# control-opto.net
KiCad netlist of a schematic drawn in EAGLE
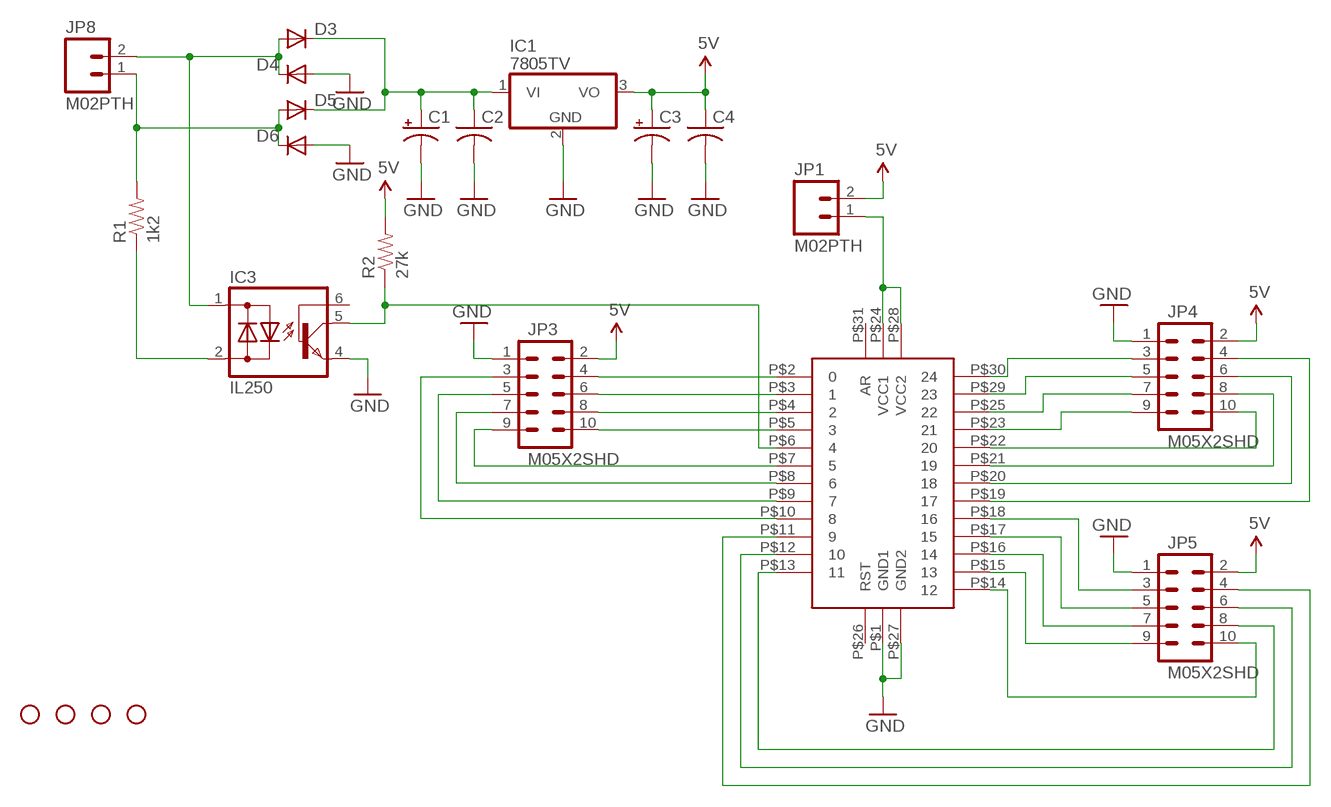
[diagram p0: schematic, sheet 1]

(export (version "E")
  (design (tool "Eeschema 10.0.6"))
  (components
    (comp (ref "C1")
      (value "CPOL-USE3.5-10")
      (footprint "eagle-import:E3,5-10")
      (libsource (lib "eagle-import") (part "CPOL-USE3.5-10"))
    )
    (comp (ref "C2")
      (value "C-US025-030X050")
      (footprint "eagle-import:C025-030X050")
      (libsource (lib "eagle-import") (part "C-US025-030X050"))
    )
    (comp (ref "C3")
      (value "CPOL-USE3.5-10")
      (footprint "eagle-import:E3,5-10")
      (libsource (lib "eagle-import") (part "CPOL-USE3.5-10"))
    )
    (comp (ref "C4")
      (value "C-US025-030X050")
      (footprint "eagle-import:C025-030X050")
      (libsource (lib "eagle-import") (part "C-US025-030X050"))
    )
    (comp (ref "D3")
      (value "DIODEPTH")
      (footprint "eagle-import:DIODE-1N4001")
      (libsource (lib "eagle-import") (part "DIODEPTH"))
    )
    (comp (ref "D4")
      (value "DIODEPTH")
      (footprint "eagle-import:DIODE-1N4001")
      (libsource (lib "eagle-import") (part "DIODEPTH"))
    )
    (comp (ref "D5")
      (value "DIODEPTH")
      (footprint "eagle-import:DIODE-1N4001")
      (libsource (lib "eagle-import") (part "DIODEPTH"))
    )
    (comp (ref "D6")
      (value "DIODEPTH")
      (footprint "eagle-import:DIODE-1N4001")
      (libsource (lib "eagle-import") (part "DIODEPTH"))
    )
    (comp (ref "IC1")
      (value "7805TV")
      (footprint "eagle-import:TO220V")
      (libsource (lib "eagle-import") (part "78TV05"))
    )
    (comp (ref "IC2")
      (value "TEENSY2")
      (footprint "eagle-import:TEENSY2")
      (libsource (lib "eagle-import") (part "TEENSY2"))
    )
    (comp (ref "IC3")
      (value "IL250")
      (footprint "eagle-import:DIL06")
      (fields (field (name "MF") "VISHAY/TELEFUNKEN"))
      (libsource (lib "eagle-import") (part "IL250"))
    )
    (comp (ref "JP1")
      (value "M02PTH")
      (footprint "eagle-import:1X02")
      (libsource (lib "eagle-import") (part "M02PTH"))
    )
    (comp (ref "JP3")
      (value "M05X2SHD")
      (footprint "eagle-import:2X5-SHROUDED")
      (libsource (lib "eagle-import") (part "M05X2SHD"))
    )
    (comp (ref "JP4")
      (value "M05X2SHD")
      (footprint "eagle-import:2X5-SHROUDED")
      (libsource (lib "eagle-import") (part "M05X2SHD"))
    )
    (comp (ref "JP5")
      (value "M05X2SHD")
      (footprint "eagle-import:2X5-SHROUDED")
      (libsource (lib "eagle-import") (part "M05X2SHD"))
    )
    (comp (ref "JP8")
      (value "M02PTH")
      (footprint "eagle-import:1X02")
      (libsource (lib "eagle-import") (part "M02PTH"))
    )
    (comp (ref "R1")
      (value "1k2")
      (footprint "eagle-import:AXIAL-0.4")
      (libsource (lib "eagle-import") (part "RESISTORPTH-1/4W"))
    )
    (comp (ref "R2")
      (value "27k")
      (footprint "eagle-import:AXIAL-0.4")
      (libsource (lib "eagle-import") (part "RESISTORPTH-1/4W"))
    )
    (comp (ref "STANDOFF1")
      (value "STAND-OFF")
      (footprint "eagle-import:STAND-OFF")
      (libsource (lib "eagle-import") (part "STAND-OFF"))
    )
    (comp (ref "STANDOFF2")
      (value "STAND-OFF")
      (footprint "eagle-import:STAND-OFF")
      (libsource (lib "eagle-import") (part "STAND-OFF"))
    )
    (comp (ref "STANDOFF3")
      (value "STAND-OFF")
      (footprint "eagle-import:STAND-OFF")
      (libsource (lib "eagle-import") (part "STAND-OFF"))
    )
    (comp (ref "STANDOFF4")
      (value "STAND-OFF")
      (footprint "eagle-import:STAND-OFF")
      (libsource (lib "eagle-import") (part "STAND-OFF"))
    )
  )
  (nets
    (net (code "1") (name "5V") (class "Default")
      (node (ref "C3") (pin "+") (pinfunction "+_+") (pintype "passive"))
      (node (ref "C4") (pin "1") (pinfunction "1_1") (pintype "passive"))
      (node (ref "IC1") (pin "3") (pinfunction "VO_3") (pintype "passive"))
      (node (ref "JP1") (pin "2") (pinfunction "2_2") (pintype "passive"))
      (node (ref "JP3") (pin "2") (pinfunction "2_2") (pintype "passive"))
      (node (ref "JP4") (pin "2") (pinfunction "2_2") (pintype "passive"))
      (node (ref "JP5") (pin "2") (pinfunction "2_2") (pintype "passive"))
      (node (ref "R2") (pin "P$2") (pinfunction "2_P$2") (pintype "passive"))
    )
    (net (code "2") (name "GND") (class "Default")
      (node (ref "C1") (pin "-") (pinfunction "-_-") (pintype "passive"))
      (node (ref "C2") (pin "2") (pinfunction "2_2") (pintype "passive"))
      (node (ref "C3") (pin "-") (pinfunction "-_-") (pintype "passive"))
      (node (ref "C4") (pin "2") (pinfunction "2_2") (pintype "passive"))
      (node (ref "D4") (pin "A") (pinfunction "A_A") (pintype "passive"))
      (node (ref "D6") (pin "A") (pinfunction "A_A") (pintype "passive"))
      (node (ref "IC1") (pin "2") (pinfunction "GND_2") (pintype "passive"))
      (node (ref "IC2") (pin "P$1") (pinfunction "GND1_P$1") (pintype "bidirectional"))
      (node (ref "IC2") (pin "P$27") (pinfunction "GND2_P$27") (pintype "bidirectional"))
      (node (ref "IC3") (pin "4") (pinfunction "E_4") (pintype "passive"))
      (node (ref "JP3") (pin "1") (pinfunction "1_1") (pintype "passive"))
      (node (ref "JP4") (pin "1") (pinfunction "1_1") (pintype "passive"))
      (node (ref "JP5") (pin "1") (pinfunction "1_1") (pintype "passive"))
    )
    (net (code "3") (name "Net-(IC1-VI)") (class "Default")
      (node (ref "C1") (pin "+") (pinfunction "+_+") (pintype "passive"))
      (node (ref "C2") (pin "1") (pinfunction "1_1") (pintype "passive"))
      (node (ref "D3") (pin "C") (pinfunction "C_C") (pintype "passive"))
      (node (ref "D5") (pin "C") (pinfunction "C_C") (pintype "passive"))
      (node (ref "IC1") (pin "1") (pinfunction "VI_1") (pintype "input"))
    )
    (net (code "4") (name "Net-(IC2-0)") (class "Default")
      (node (ref "IC2") (pin "P$2") (pinfunction "0_P$2") (pintype "bidirectional"))
      (node (ref "JP3") (pin "4") (pinfunction "4_4") (pintype "passive"))
    )
    (net (code "5") (name "Net-(IC2-1)") (class "Default")
      (node (ref "IC2") (pin "P$3") (pinfunction "1_P$3") (pintype "bidirectional"))
      (node (ref "JP3") (pin "6") (pinfunction "6_6") (pintype "passive"))
    )
    (net (code "6") (name "Net-(IC2-2)") (class "Default")
      (node (ref "IC2") (pin "P$4") (pinfunction "2_P$4") (pintype "bidirectional"))
      (node (ref "JP3") (pin "8") (pinfunction "8_8") (pintype "passive"))
    )
    (net (code "7") (name "Net-(IC2-3)") (class "Default")
      (node (ref "IC2") (pin "P$5") (pinfunction "3_P$5") (pintype "bidirectional"))
      (node (ref "JP3") (pin "10") (pinfunction "10_10") (pintype "passive"))
    )
    (net (code "8") (name "Net-(IC2-4)") (class "Default")
      (node (ref "IC2") (pin "P$6") (pinfunction "4_P$6") (pintype "bidirectional"))
      (node (ref "IC3") (pin "5") (pinfunction "C_5") (pintype "passive"))
      (node (ref "R2") (pin "P$1") (pinfunction "1_P$1") (pintype "passive"))
    )
    (net (code "9") (name "Net-(IC2-5)") (class "Default")
      (node (ref "IC2") (pin "P$7") (pinfunction "5_P$7") (pintype "bidirectional"))
      (node (ref "JP3") (pin "9") (pinfunction "9_9") (pintype "passive"))
    )
    (net (code "10") (name "Net-(IC2-6)") (class "Default")
      (node (ref "IC2") (pin "P$8") (pinfunction "6_P$8") (pintype "bidirectional"))
      (node (ref "JP3") (pin "7") (pinfunction "7_7") (pintype "passive"))
    )
    (net (code "11") (name "Net-(IC2-7)") (class "Default")
      (node (ref "IC2") (pin "P$9") (pinfunction "7_P$9") (pintype "bidirectional"))
      (node (ref "JP3") (pin "5") (pinfunction "5_5") (pintype "passive"))
    )
    (net (code "12") (name "Net-(IC2-8)") (class "Default")
      (node (ref "IC2") (pin "P$10") (pinfunction "8_P$10") (pintype "bidirectional"))
      (node (ref "JP3") (pin "3") (pinfunction "3_3") (pintype "passive"))
    )
    (net (code "13") (name "Net-(IC2-9)") (class "Default")
      (node (ref "IC2") (pin "P$11") (pinfunction "9_P$11") (pintype "bidirectional"))
      (node (ref "JP5") (pin "4") (pinfunction "4_4") (pintype "passive"))
    )
    (net (code "14") (name "Net-(IC2-10)") (class "Default")
      (node (ref "IC2") (pin "P$12") (pinfunction "10_P$12") (pintype "bidirectional"))
      (node (ref "JP5") (pin "6") (pinfunction "6_6") (pintype "passive"))
    )
    (net (code "15") (name "Net-(IC2-11)") (class "Default")
      (node (ref "IC2") (pin "P$13") (pinfunction "11_P$13") (pintype "bidirectional"))
      (node (ref "JP5") (pin "8") (pinfunction "8_8") (pintype "passive"))
    )
    (net (code "16") (name "Net-(IC2-12)") (class "Default")
      (node (ref "IC2") (pin "P$14") (pinfunction "12_P$14") (pintype "bidirectional"))
      (node (ref "JP5") (pin "10") (pinfunction "10_10") (pintype "passive"))
    )
    (net (code "17") (name "Net-(IC2-13)") (class "Default")
      (node (ref "IC2") (pin "P$15") (pinfunction "13_P$15") (pintype "bidirectional"))
      (node (ref "JP5") (pin "9") (pinfunction "9_9") (pintype "passive"))
    )
    (net (code "18") (name "Net-(IC2-14)") (class "Default")
      (node (ref "IC2") (pin "P$16") (pinfunction "14_P$16") (pintype "bidirectional"))
      (node (ref "JP5") (pin "7") (pinfunction "7_7") (pintype "passive"))
    )
    (net (code "19") (name "Net-(IC2-15)") (class "Default")
      (node (ref "IC2") (pin "P$17") (pinfunction "15_P$17") (pintype "bidirectional"))
      (node (ref "JP5") (pin "5") (pinfunction "5_5") (pintype "passive"))
    )
    (net (code "20") (name "Net-(IC2-16)") (class "Default")
      (node (ref "IC2") (pin "P$18") (pinfunction "16_P$18") (pintype "bidirectional"))
      (node (ref "JP5") (pin "3") (pinfunction "3_3") (pintype "passive"))
    )
    (net (code "21") (name "Net-(IC2-17)") (class "Default")
      (node (ref "IC2") (pin "P$19") (pinfunction "17_P$19") (pintype "bidirectional"))
      (node (ref "JP4") (pin "4") (pinfunction "4_4") (pintype "passive"))
    )
    (net (code "22") (name "Net-(IC2-18)") (class "Default")
      (node (ref "IC2") (pin "P$20") (pinfunction "18_P$20") (pintype "bidirectional"))
      (node (ref "JP4") (pin "6") (pinfunction "6_6") (pintype "passive"))
    )
    (net (code "23") (name "Net-(IC2-19)") (class "Default")
      (node (ref "IC2") (pin "P$21") (pinfunction "19_P$21") (pintype "bidirectional"))
      (node (ref "JP4") (pin "8") (pinfunction "8_8") (pintype "passive"))
    )
    (net (code "24") (name "Net-(IC2-20)") (class "Default")
      (node (ref "IC2") (pin "P$22") (pinfunction "20_P$22") (pintype "bidirectional"))
      (node (ref "JP4") (pin "10") (pinfunction "10_10") (pintype "passive"))
    )
    (net (code "25") (name "Net-(IC2-21)") (class "Default")
      (node (ref "IC2") (pin "P$23") (pinfunction "21_P$23") (pintype "bidirectional"))
      (node (ref "JP4") (pin "9") (pinfunction "9_9") (pintype "passive"))
    )
    (net (code "26") (name "Net-(IC2-22)") (class "Default")
      (node (ref "IC2") (pin "P$25") (pinfunction "22_P$25") (pintype "bidirectional"))
      (node (ref "JP4") (pin "7") (pinfunction "7_7") (pintype "passive"))
    )
    (net (code "27") (name "Net-(IC2-23)") (class "Default")
      (node (ref "IC2") (pin "P$29") (pinfunction "23_P$29") (pintype "bidirectional"))
      (node (ref "JP4") (pin "5") (pinfunction "5_5") (pintype "passive"))
    )
    (net (code "28") (name "Net-(IC2-24)") (class "Default")
      (node (ref "IC2") (pin "P$30") (pinfunction "24_P$30") (pintype "bidirectional"))
      (node (ref "JP4") (pin "3") (pinfunction "3_3") (pintype "passive"))
    )
    (net (code "29") (name "Net-(IC2-VCC1)") (class "Default")
      (node (ref "IC2") (pin "P$24") (pinfunction "VCC1_P$24") (pintype "bidirectional"))
      (node (ref "IC2") (pin "P$28") (pinfunction "VCC2_P$28") (pintype "bidirectional"))
      (node (ref "JP1") (pin "1") (pinfunction "1_1") (pintype "passive"))
    )
    (net (code "30") (name "Net-(IC3-AC1)") (class "Default")
      (node (ref "D3") (pin "A") (pinfunction "A_A") (pintype "passive"))
      (node (ref "D4") (pin "C") (pinfunction "C_C") (pintype "passive"))
      (node (ref "IC3") (pin "1") (pinfunction "AC1_1") (pintype "passive"))
      (node (ref "JP8") (pin "2") (pinfunction "2_2") (pintype "passive"))
    )
    (net (code "31") (name "Net-(IC3-AC2)") (class "Default")
      (node (ref "IC3") (pin "2") (pinfunction "AC2_2") (pintype "passive"))
      (node (ref "R1") (pin "P$1") (pinfunction "1_P$1") (pintype "passive"))
    )
    (net (code "32") (name "Net-(R1-2)") (class "Default")
      (node (ref "D5") (pin "A") (pinfunction "A_A") (pintype "passive"))
      (node (ref "D6") (pin "C") (pinfunction "C_C") (pintype "passive"))
      (node (ref "JP8") (pin "1") (pinfunction "1_1") (pintype "passive"))
      (node (ref "R1") (pin "P$2") (pinfunction "2_P$2") (pintype "passive"))
    )
    (net (code "33") (name "unconnected-(IC2-AR-PadP$31)") (class "Default")
      (node (ref "IC2") (pin "P$31") (pinfunction "AR_P$31") (pintype "bidirectional"))
    )
    (net (code "34") (name "unconnected-(IC2-RST-PadP$26)") (class "Default")
      (node (ref "IC2") (pin "P$26") (pinfunction "RST_P$26") (pintype "bidirectional"))
    )
    (net (code "35") (name "unconnected-(IC3-B-Pad6)") (class "Default")
      (node (ref "IC3") (pin "6") (pinfunction "B_6") (pintype "passive"))
    )
  )
)
